# ADC.net
KiCad netlist of a schematic drawn in Altium Designer
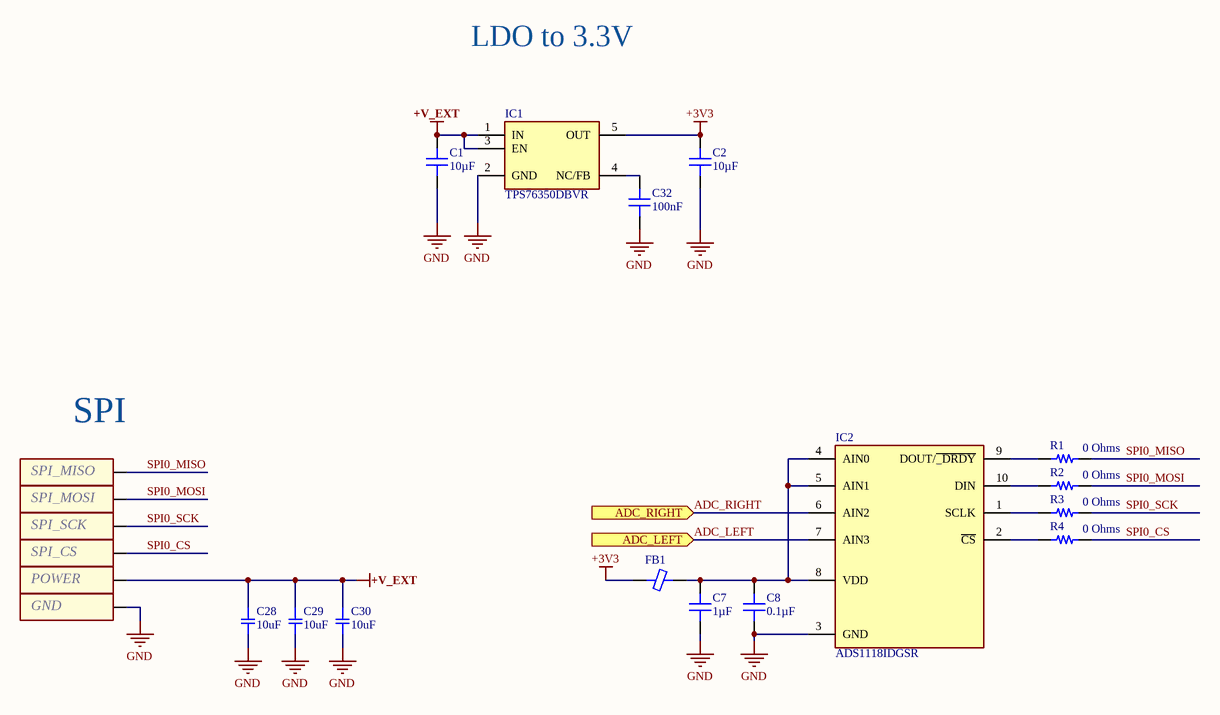
[diagram p0: ADC.SchDoc]

(export (version "E")
  (design (tool "Eeschema 10.0.6"))
  (components
    (comp (ref "C1")
      (value "10µF")
      (footprint "CAP 0603_1608")
      (description "CAP CER 0.1UF 10V X7R 0603")
      (fields (field (name "PART NUMBER") "100X14W104MV4T"))
      (libsource (lib "Celestial Altium Library - altium_library") (part "Capacitor"))
    )
    (comp (ref "C2")
      (value "10µF")
      (footprint "CAP 0603_1608")
      (description "CAP CER 0.1UF 10V X7R 0603")
      (fields (field (name "PART NUMBER") "100X14W104MV4T"))
      (libsource (lib "Celestial Altium Library - altium_library") (part "Capacitor"))
    )
    (comp (ref "C7")
      (value "1µF")
      (footprint "CAP 0603_1608")
      (description "CAP CER 0.1UF 10V X7R 0603")
      (fields (field (name "PART NUMBER") "100X14W104MV4T"))
      (libsource (lib "Celestial Altium Library - altium_library") (part "Capacitor"))
    )
    (comp (ref "C8")
      (value "0.1µF")
      (footprint "CAP 0603_1608")
      (description "CAP CER 0.1UF 10V X7R 0603")
      (fields (field (name "PART NUMBER") "100X14W104MV4T"))
      (libsource (lib "Celestial Altium Library - altium_library") (part "Capacitor"))
    )
    (comp (ref "C28")
      (value "10uF")
      (footprint "SMD-0805C")
      (description "CAP CER 10UF 10V X7R 0805")
      (fields
        (field (name "PART NUMBER") "GRJ21BR71A106KE01L")
        (field (name "DIGI-KEY PART NUMBER") "490-10919-1-ND")
      )
      (libsource (lib "cap_murata") (part "CAPACITOR"))
    )
    (comp (ref "C29")
      (value "10uF")
      (footprint "SMD-0805C")
      (description "CAP CER 10UF 10V X7R 0805")
      (fields
        (field (name "PART NUMBER") "GRJ21BR71A106KE01L")
        (field (name "DIGI-KEY PART NUMBER") "490-10919-1-ND")
      )
      (libsource (lib "cap_murata") (part "CAPACITOR"))
    )
    (comp (ref "C30")
      (value "10uF")
      (footprint "SMD-0805C")
      (description "CAP CER 10UF 10V X7R 0805")
      (fields
        (field (name "PART NUMBER") "GRJ21BR71A106KE01L")
        (field (name "DIGI-KEY PART NUMBER") "490-10919-1-ND")
      )
      (libsource (lib "cap_murata") (part "CAPACITOR"))
    )
    (comp (ref "C32")
      (value "100nF")
      (footprint "CAP 0603_1608")
      (description "CAP CER 0.1UF 10V X7R 0603")
      (fields (field (name "PART NUMBER") "100X14W104MV4T"))
      (libsource (lib "Celestial Altium Library - altium_library") (part "Capacitor"))
    )
    (comp (ref "FB1")
      (value "~")
      (footprint "FER 0603_1608")
      (description "FERRITE BEAD 0603 1LN")
      (fields (field (name "PART NUMBER") "2506031217H0"))
      (libsource (lib "Celestial Altium Library - altium_library") (part "Ferrite Chip"))
    )
    (comp (ref "IC1")
      (value "TPS76350DBVR")
      (footprint "SamacSys:SOT95P280X145-5N")
      (description "Integrated Circuit")
      (fields (field (name "MOUSER PART NUMBER") "595-TPS76350DBVR"))
      (libsource (lib "SamacSys") (part "TPS76350DBVR"))
    )
    (comp (ref "IC2")
      (value "ADS1118IDGSR")
      (footprint "SamacSys:SOP50P490X110-10N")
      (description "Integrated Circuit")
      (fields (field (name "MOUSER PART NUMBER") "595-ADS1118IDGSR"))
      (libsource (lib "SamacSys") (part "ADS1118IDGSR"))
    )
    (comp (ref "R1")
      (value "0 Ohms")
      (footprint "PCB - RESISTOR - CHIP - STACKPOLE CSR0603:RES 0603_1608")
      (description "RES 100 OHM 0.1% 1/16W 0603")
      (fields (field (name "PART NUMBER") "RNCS0603BKE100R"))
      (libsource (lib "Celestial Altium Library - altium_library") (part "Resistor"))
    )
    (comp (ref "R2")
      (value "0 Ohms")
      (footprint "PCB - RESISTOR - CHIP - STACKPOLE CSR0603:RES 0603_1608")
      (description "RES 100 OHM 0.1% 1/16W 0603")
      (fields (field (name "PART NUMBER") "RNCS0603BKE100R"))
      (libsource (lib "Celestial Altium Library - altium_library") (part "Resistor"))
    )
    (comp (ref "R3")
      (value "0 Ohms")
      (footprint "PCB - RESISTOR - CHIP - STACKPOLE CSR0603:RES 0603_1608")
      (description "RES 100 OHM 0.1% 1/16W 0603")
      (fields (field (name "PART NUMBER") "RNCS0603BKE100R"))
      (libsource (lib "Celestial Altium Library - altium_library") (part "Resistor"))
    )
    (comp (ref "R4")
      (value "0 Ohms")
      (footprint "PCB - RESISTOR - CHIP - STACKPOLE CSR0603:RES 0603_1608")
      (description "RES 100 OHM 0.1% 1/16W 0603")
      (fields (field (name "PART NUMBER") "RNCS0603BKE100R"))
      (libsource (lib "Celestial Altium Library - altium_library") (part "Resistor"))
    )
    (comp (ref "X1")
      (value "SPI_MISO")
      (footprint "PLS-1")
      (fields (field (name "NAME") "SPI_MISO") (field (name "MANUFACTURER") "KHADB"))
      (libsource (lib "CoinSensor _TLV333  v1.0") (part "IN-OUT pin"))
    )
    (comp (ref "X2")
      (value "SPI_MISO")
      (footprint "PLS-1")
      (fields (field (name "NAME") "SPI_MOSI") (field (name "MANUFACTURER") "KHADB"))
      (libsource (lib "CoinSensor _TLV333  v1.0") (part "IN-OUT pin"))
    )
    (comp (ref "X3")
      (value "SPI_MISO")
      (footprint "PLS-1")
      (fields (field (name "NAME") "SPI_SCK") (field (name "MANUFACTURER") "KHADB"))
      (libsource (lib "CoinSensor _TLV333  v1.0") (part "IN-OUT pin"))
    )
    (comp (ref "X4")
      (value "SPI_MISO")
      (footprint "PLS-1")
      (fields (field (name "NAME") "SPI_CS") (field (name "MANUFACTURER") "KHADB"))
      (libsource (lib "CoinSensor _TLV333  v1.0") (part "IN-OUT pin"))
    )
    (comp (ref "X5")
      (value "SPI_MISO")
      (footprint "PLS-1")
      (fields (field (name "NAME") "POWER") (field (name "MANUFACTURER") "KHADB"))
      (libsource (lib "CoinSensor _TLV333  v1.0") (part "IN-OUT pin"))
    )
    (comp (ref "X6")
      (value "SPI_MISO")
      (footprint "PLS-1")
      (fields (field (name "NAME") "GND") (field (name "MANUFACTURER") "KHADB"))
      (libsource (lib "CoinSensor _TLV333  v1.0") (part "IN-OUT pin"))
    )
  )
  (nets
    (net (code "1") (name "+3V3") (class "Default")
      (node (ref "C2") (pin "2") (pinfunction "2_2") (pintype "passive"))
      (node (ref "FB1") (pin "1") (pinfunction "1_1") (pintype "passive"))
      (node (ref "IC1") (pin "5") (pinfunction "OUT_5") (pintype "passive"))
    )
    (net (code "2") (name "+V_EXT") (class "Default")
      (node (ref "C1") (pin "2") (pinfunction "2_2") (pintype "passive"))
      (node (ref "C28") (pin "1") (pinfunction "1_1") (pintype "passive"))
      (node (ref "C29") (pin "1") (pinfunction "1_1") (pintype "passive"))
      (node (ref "C30") (pin "1") (pinfunction "1_1") (pintype "passive"))
      (node (ref "IC1") (pin "1") (pinfunction "IN_1") (pintype "passive"))
      (node (ref "IC1") (pin "3") (pinfunction "EN_3") (pintype "passive"))
      (node (ref "X5") (pin "1") (pinfunction "1_1") (pintype "passive"))
    )
    (net (code "3") (name "/ADC_LEFT") (class "Default")
      (node (ref "IC2") (pin "7") (pinfunction "AIN3_7") (pintype "passive"))
    )
    (net (code "4") (name "/ADC_RIGHT") (class "Default")
      (node (ref "IC2") (pin "6") (pinfunction "AIN2_6") (pintype "passive"))
    )
    (net (code "5") (name "/SPI0_CS") (class "Default")
      (node (ref "R4") (pin "1") (pinfunction "1_1") (pintype "passive"))
      (node (ref "X4") (pin "1") (pinfunction "1_1") (pintype "passive"))
    )
    (net (code "6") (name "/SPI0_MISO") (class "Default")
      (node (ref "R1") (pin "1") (pinfunction "1_1") (pintype "passive"))
      (node (ref "X1") (pin "1") (pinfunction "1_1") (pintype "passive"))
    )
    (net (code "7") (name "/SPI0_MOSI") (class "Default")
      (node (ref "R2") (pin "1") (pinfunction "1_1") (pintype "passive"))
      (node (ref "X2") (pin "1") (pinfunction "1_1") (pintype "passive"))
    )
    (net (code "8") (name "/SPI0_SCK") (class "Default")
      (node (ref "R3") (pin "1") (pinfunction "1_1") (pintype "passive"))
      (node (ref "X3") (pin "1") (pinfunction "1_1") (pintype "passive"))
    )
    (net (code "9") (name "GND") (class "Default")
      (node (ref "C1") (pin "1") (pinfunction "1_1") (pintype "passive"))
      (node (ref "C2") (pin "1") (pinfunction "1_1") (pintype "passive"))
      (node (ref "C28") (pin "2") (pinfunction "2_2") (pintype "passive"))
      (node (ref "C29") (pin "2") (pinfunction "2_2") (pintype "passive"))
      (node (ref "C30") (pin "2") (pinfunction "2_2") (pintype "passive"))
      (node (ref "C32") (pin "1") (pinfunction "1_1") (pintype "passive"))
      (node (ref "C7") (pin "1") (pinfunction "1_1") (pintype "passive"))
      (node (ref "C8") (pin "1") (pinfunction "1_1") (pintype "passive"))
      (node (ref "IC1") (pin "2") (pinfunction "GND_2") (pintype "passive"))
      (node (ref "IC2") (pin "3") (pinfunction "GND_3") (pintype "passive"))
      (node (ref "X6") (pin "1") (pinfunction "1_1") (pintype "passive"))
    )
    (net (code "10") (name "Net-(IC1-NC{slash}FB)") (class "Default")
      (node (ref "C32") (pin "2") (pinfunction "2_2") (pintype "passive"))
      (node (ref "IC1") (pin "4") (pinfunction "NC/FB_4") (pintype "passive"))
    )
    (net (code "11") (name "Net-(IC2-AIN0)") (class "Default")
      (node (ref "C7") (pin "2") (pinfunction "2_2") (pintype "passive"))
      (node (ref "C8") (pin "2") (pinfunction "2_2") (pintype "passive"))
      (node (ref "FB1") (pin "2") (pinfunction "2_2") (pintype "passive"))
      (node (ref "IC2") (pin "4") (pinfunction "AIN0_4") (pintype "passive"))
      (node (ref "IC2") (pin "5") (pinfunction "AIN1_5") (pintype "passive"))
      (node (ref "IC2") (pin "8") (pinfunction "VDD_8") (pintype "passive"))
    )
    (net (code "12") (name "Net-(IC2-DIN)") (class "Default")
      (node (ref "IC2") (pin "10") (pinfunction "DIN_10") (pintype "passive"))
      (node (ref "R2") (pin "2") (pinfunction "2_2") (pintype "passive"))
    )
    (net (code "13") (name "Net-(IC2-DOUT{slash}~{_DRDY})") (class "Default")
      (node (ref "IC2") (pin "9") (pinfunction "DOUT/~{_DRDY}_9") (pintype "passive"))
      (node (ref "R1") (pin "2") (pinfunction "2_2") (pintype "passive"))
    )
    (net (code "14") (name "Net-(IC2-SCLK)") (class "Default")
      (node (ref "IC2") (pin "1") (pinfunction "SCLK_1") (pintype "passive"))
      (node (ref "R3") (pin "2") (pinfunction "2_2") (pintype "passive"))
    )
    (net (code "15") (name "Net-(IC2-~{CS})") (class "Default")
      (node (ref "IC2") (pin "2") (pinfunction "~{CS}_2") (pintype "passive"))
      (node (ref "R4") (pin "2") (pinfunction "2_2") (pintype "passive"))
    )
  )
)
